# keyboard.net
KiCad netlist of a schematic drawn in Altium Designer
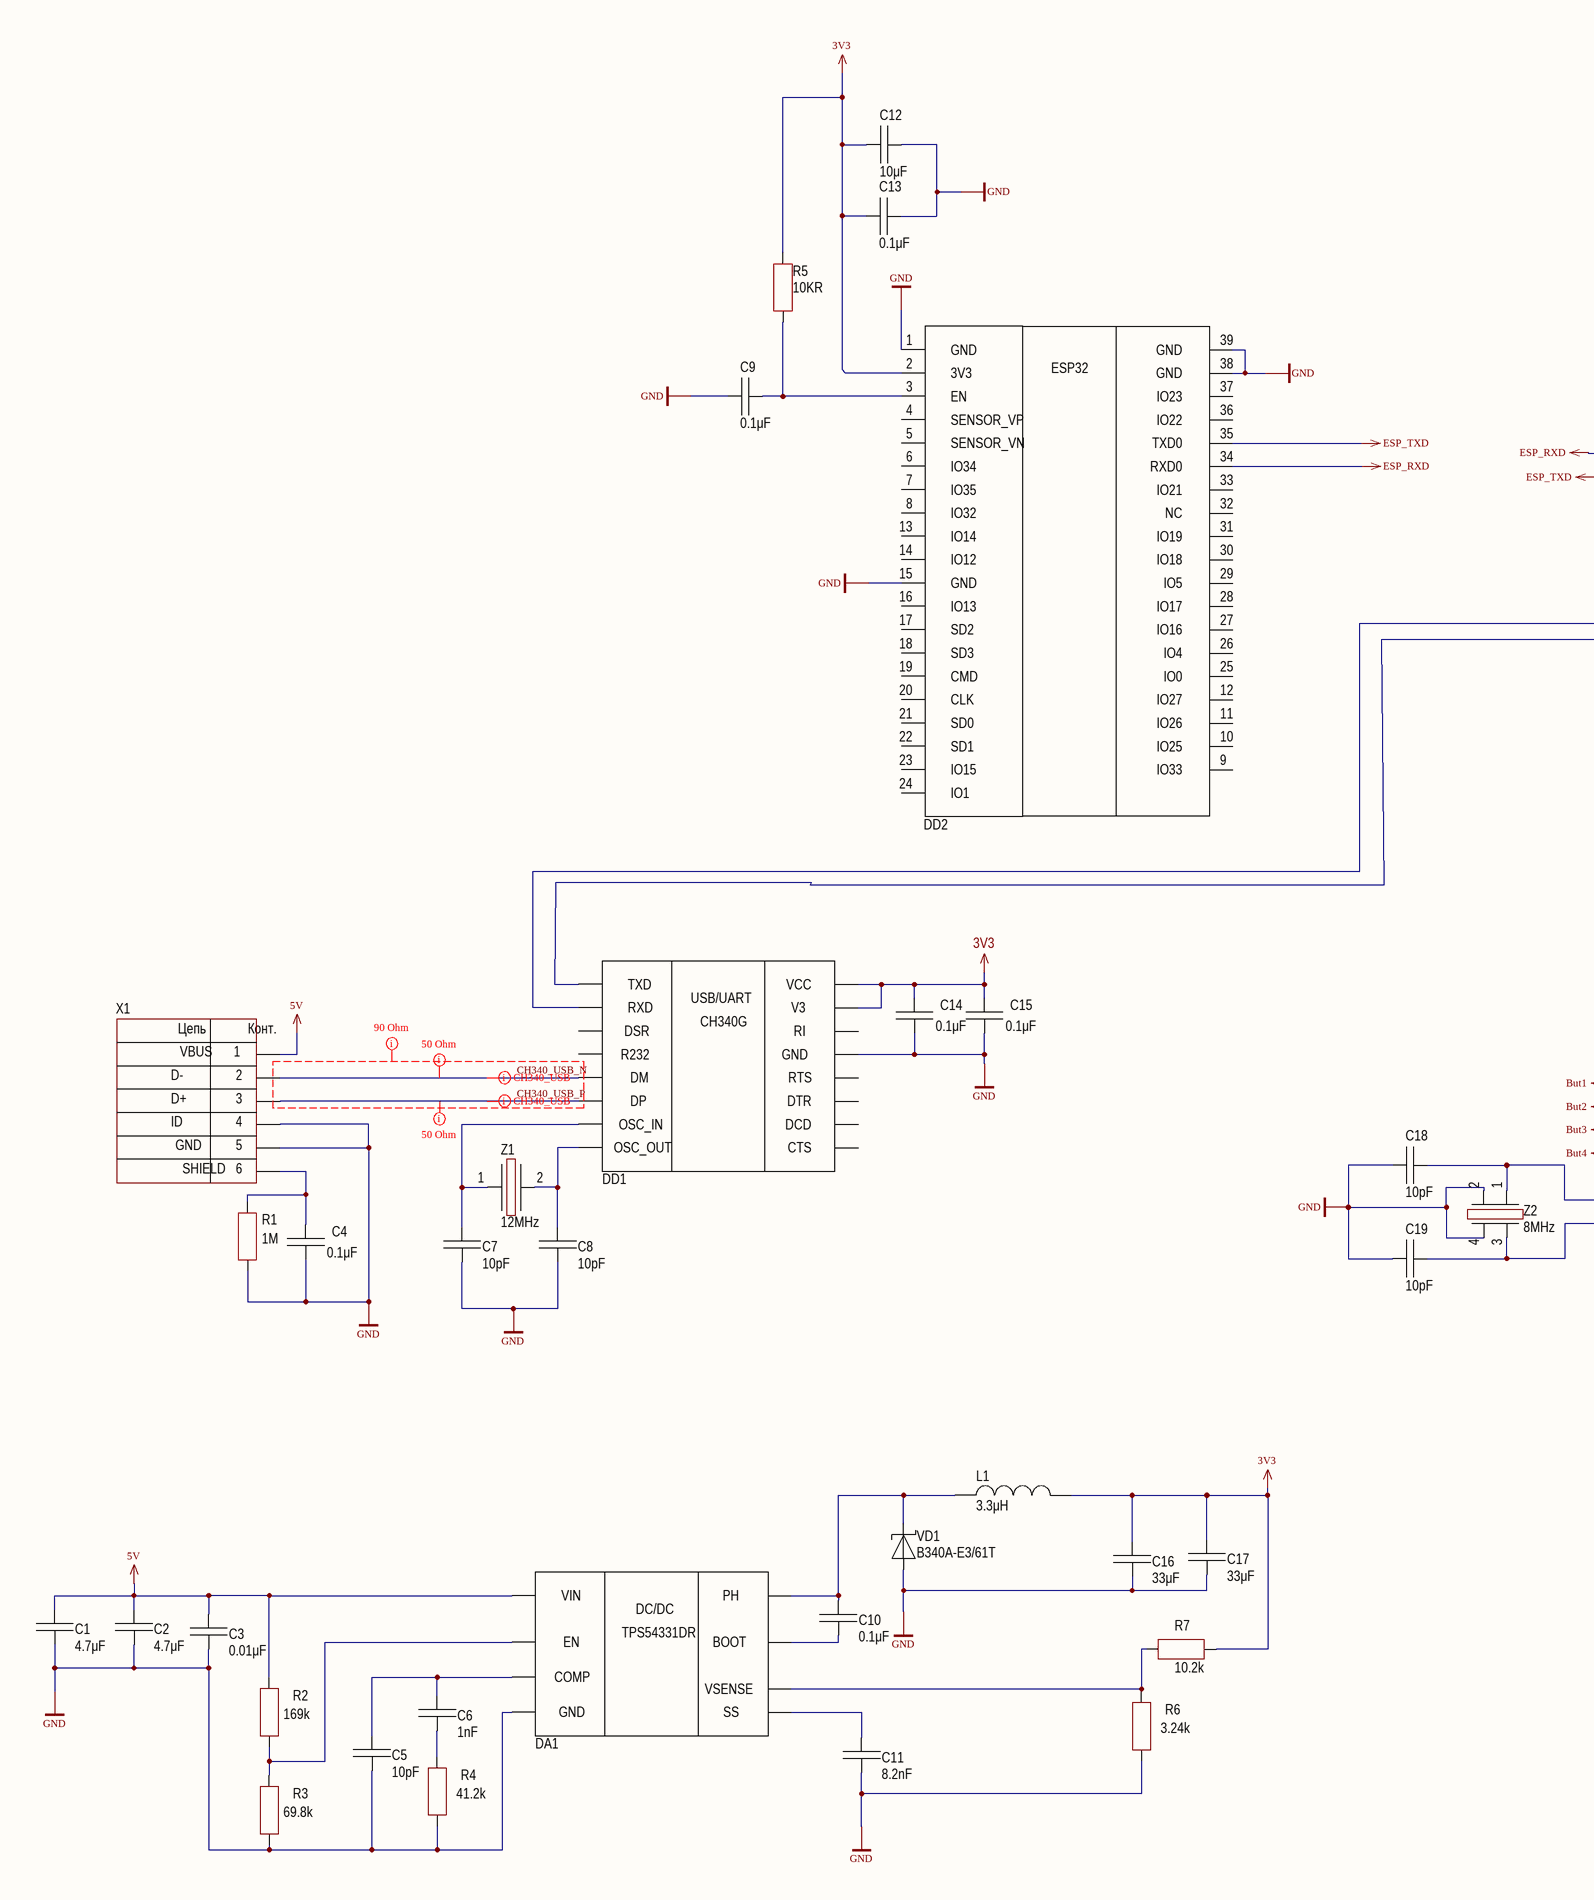
[diagram p0: keyboard.SchDoc, left]
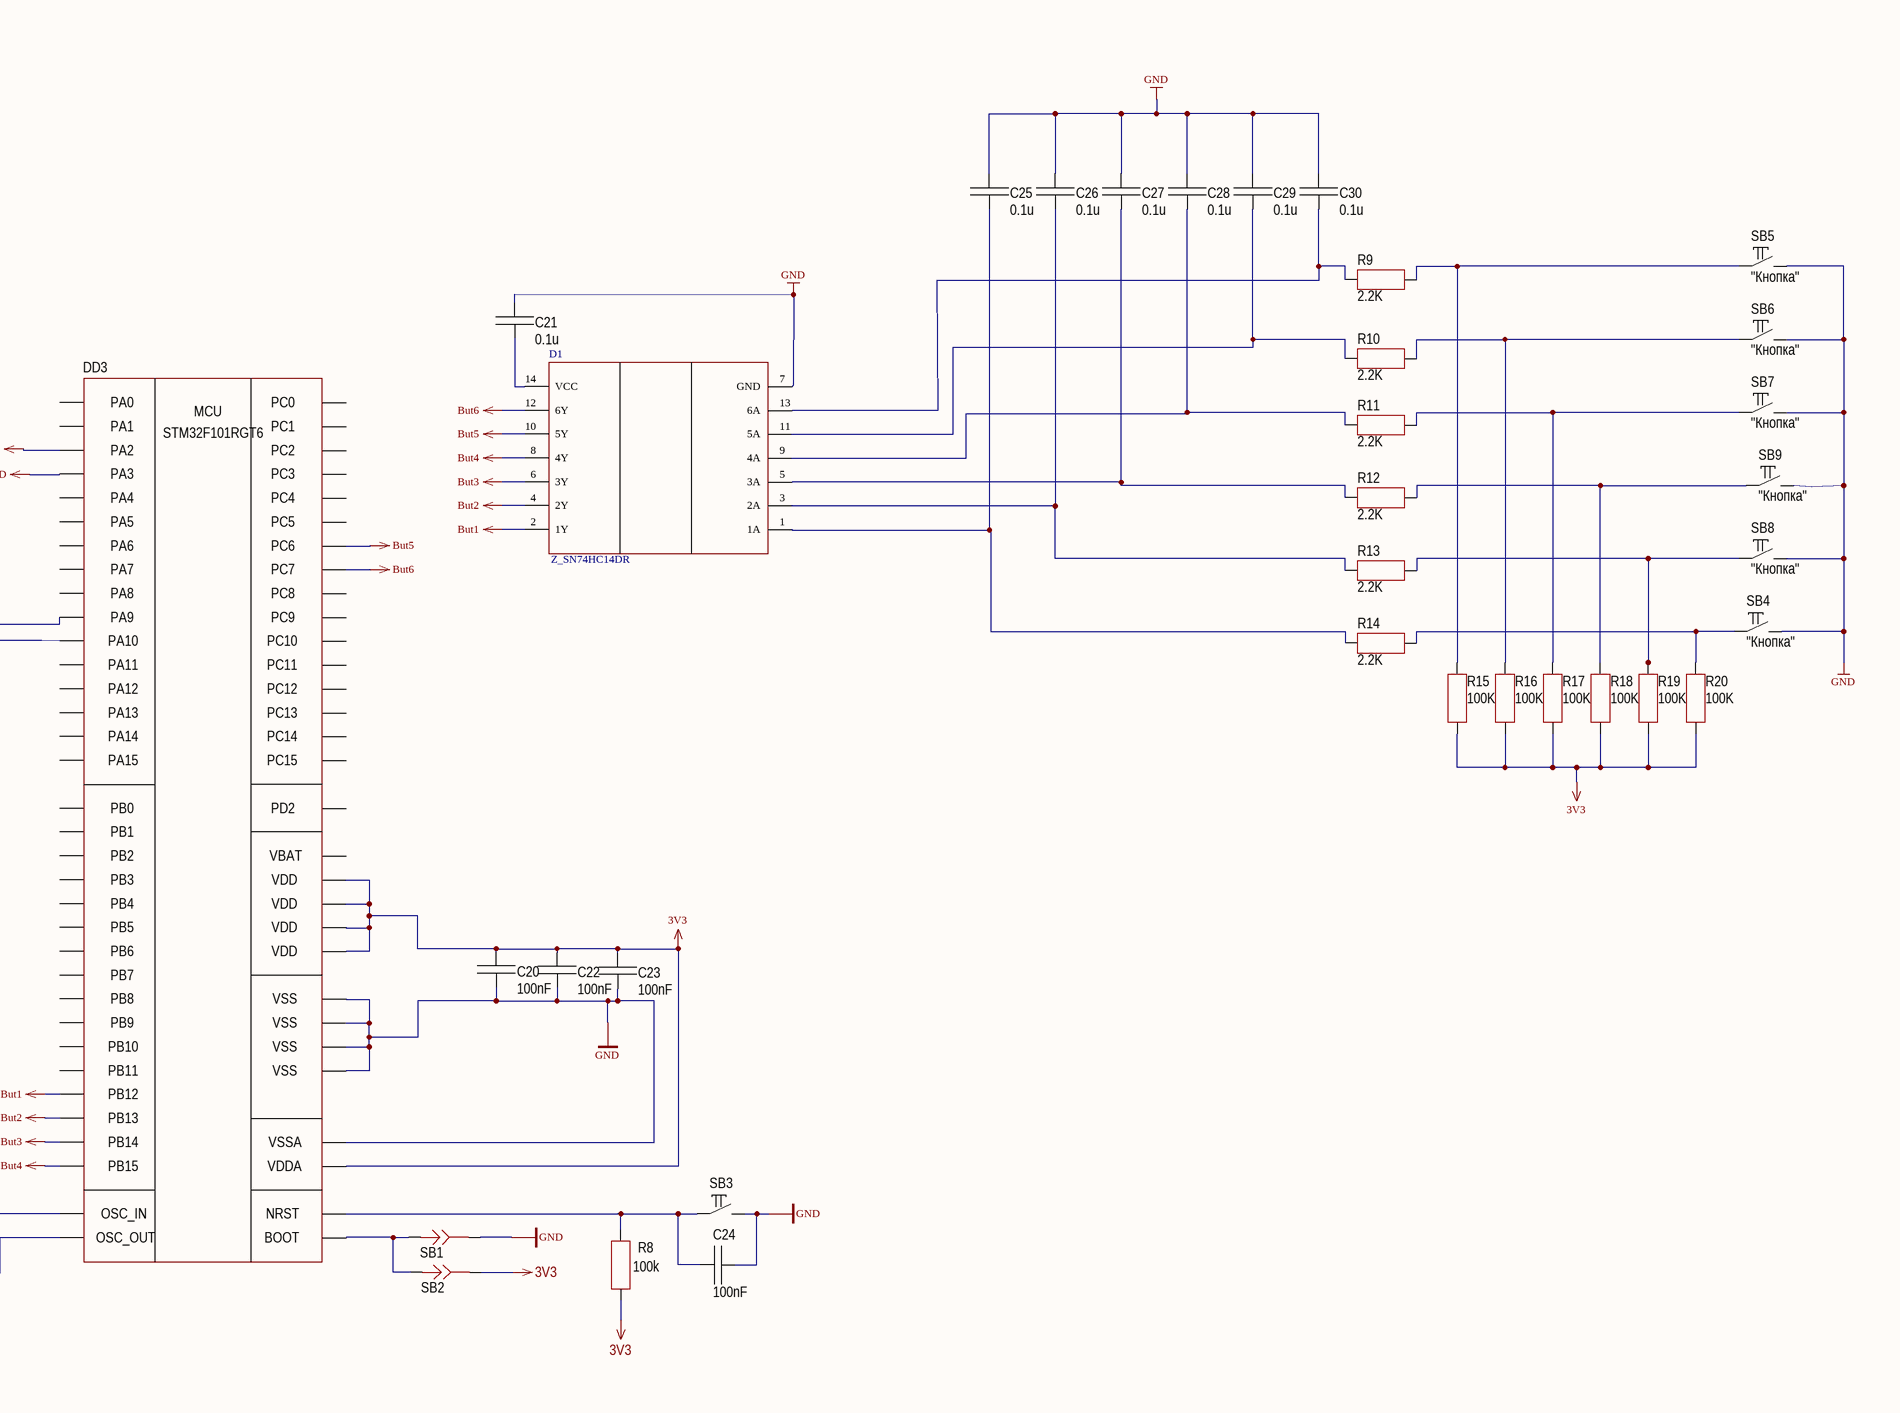
[diagram p1: keyboard.SchDoc, right]

(export (version "E")
  (design (tool "Eeschema 10.0.6"))
  (components
    (comp (ref "C1")
      (value "4.7μF")
      (footprint "CAP: 0603")
      (fields
        (field (name "VALUEMANUFACTURERPARTNUMBER") "Ceramic capacitor, 4.7μF, X7R, ±10%, 16V, 0603, -55...+125°C")
        (field (name "TOLERANCE") "±10%")
        (field (name "VOLTAGE") "16V")
      )
      (libsource (lib "Sch_camr0d") (part "CAP_CERAMIC-SMD"))
    )
    (comp (ref "C2")
      (value "4.7μF")
      (footprint "CAP: 0603")
      (fields
        (field (name "VALUEMANUFACTURERPARTNUMBER") "Ceramic capacitor, 4.7μF, X7R, ±10%, 16V, 0603, -55...+125°C")
        (field (name "TOLERANCE") "±10%")
        (field (name "VOLTAGE") "16V")
      )
      (libsource (lib "Sch_camr0d") (part "CAP_CERAMIC-SMD"))
    )
    (comp (ref "C3")
      (value "0.01μF")
      (footprint "CAP: 0603")
      (fields
        (field (name "VALUEMANUFACTURERPARTNUMBER") "Ceramic capacitor, 0.01μF, X7R, ±10%, 16V, 0603, -55...+125°C")
        (field (name "TOLERANCE") "±10%")
        (field (name "VOLTAGE") "16V")
      )
      (libsource (lib "Sch_camr0d") (part "CAP_CERAMIC-SMD"))
    )
    (comp (ref "C4")
      (value "0.1μF")
      (footprint "CAP: 0603")
      (fields
        (field (name "VALUEMANUFACTURERPARTNUMBER") "Ceramic capacitor, 0.1μF, X7R, ±10%, 16V, 0603, -55...+125°C")
        (field (name "TOLERANCE") "±10%")
        (field (name "VOLTAGE") "16V")
      )
      (libsource (lib "Sch_camr0d") (part "CAP_CERAMIC-SMD"))
    )
    (comp (ref "C5")
      (value "10pF")
      (footprint "CAP: 0603")
      (fields
        (field (name "VALUEMANUFACTURERPARTNUMBER") "Ceramic capacitor, 10pF, X7R, ±10%, 16V, 0603, -55...+125°C")
        (field (name "TOLERANCE") "±10%")
        (field (name "VOLTAGE") "16V")
      )
      (libsource (lib "Sch_camr0d") (part "CAP_CERAMIC-SMD"))
    )
    (comp (ref "C6")
      (value "1nF")
      (footprint "CAP: 0603")
      (fields
        (field (name "VALUEMANUFACTURERPARTNUMBER") "Ceramic capacitor, 1nF, X7R, ±10%, 16V, 0603, -55...+125°C")
        (field (name "TOLERANCE") "±10%")
        (field (name "VOLTAGE") "16V")
      )
      (libsource (lib "Sch_camr0d") (part "CAP_CERAMIC-SMD"))
    )
    (comp (ref "C7")
      (value "10pF")
      (footprint "CAP: 0603")
      (fields
        (field (name "VALUEMANUFACTURERPARTNUMBER") "Ceramic capacitor, 10pF, X7R, ±10%, 16V, 0603, -55...+125°C")
        (field (name "TOLERANCE") "±10%")
        (field (name "VOLTAGE") "16V")
      )
      (libsource (lib "Sch_camr0d") (part "CAP_CERAMIC-SMD"))
    )
    (comp (ref "C8")
      (value "10pF")
      (footprint "CAP: 0603")
      (fields
        (field (name "VALUEMANUFACTURERPARTNUMBER") "Ceramic capacitor, 10pF, X7R, ±10%, 16V, 0603, -55...+125°C")
        (field (name "TOLERANCE") "±10%")
        (field (name "VOLTAGE") "16V")
      )
      (libsource (lib "Sch_camr0d") (part "CAP_CERAMIC-SMD"))
    )
    (comp (ref "C9")
      (value "0.1μF")
      (footprint "CAP: 0603")
      (fields
        (field (name "VALUEMANUFACTURERPARTNUMBER") "Ceramic capacitor, 0.1μF, X7R, ±10%, 16V, 0603, -55...+125°C")
        (field (name "TOLERANCE") "±10%")
        (field (name "VOLTAGE") "16V")
      )
      (libsource (lib "Sch_camr0d") (part "CAP_CERAMIC-SMD"))
    )
    (comp (ref "C10")
      (value "0.1μF")
      (footprint "CAP: 0603")
      (fields
        (field (name "VALUEMANUFACTURERPARTNUMBER") "Ceramic capacitor, 0.1μF, X7R, ±10%, 16V, 0603, -55...+125°C")
        (field (name "TOLERANCE") "±10%")
        (field (name "VOLTAGE") "16V")
      )
      (libsource (lib "Sch_camr0d") (part "CAP_CERAMIC-SMD"))
    )
    (comp (ref "C11")
      (value "8.2nF")
      (footprint "CAP: 0603")
      (fields
        (field (name "VALUEMANUFACTURERPARTNUMBER") "Ceramic capacitor, 8.2nF, X7R, ±10%, 16V, 0603, -55...+125°C")
        (field (name "TOLERANCE") "±10%")
        (field (name "VOLTAGE") "16V")
      )
      (libsource (lib "Sch_camr0d") (part "CAP_CERAMIC-SMD"))
    )
    (comp (ref "C12")
      (value "10μF")
      (footprint "CAP: 0603")
      (fields
        (field (name "VALUEMANUFACTURERPARTNUMBER") "Ceramic capacitor, 10μF, X7R, ±10%, 16V, 0603, -55...+125°C")
        (field (name "TOLERANCE") "±10%")
        (field (name "VOLTAGE") "16V")
      )
      (libsource (lib "Sch_camr0d") (part "CAP_CERAMIC-SMD"))
    )
    (comp (ref "C13")
      (value "0.1μF")
      (footprint "CAP: 0603")
      (fields
        (field (name "VALUEMANUFACTURERPARTNUMBER") "Ceramic capacitor, 0.1μF, X7R, ±10%, 16V, 0603, -55...+125°C")
        (field (name "TOLERANCE") "±10%")
        (field (name "VOLTAGE") "16V")
      )
      (libsource (lib "Sch_camr0d") (part "CAP_CERAMIC-SMD"))
    )
    (comp (ref "C14")
      (value "0.1μF")
      (footprint "CAP: 0603")
      (fields
        (field (name "VALUEMANUFACTURERPARTNUMBER") "Ceramic capacitor, 0.1μF, X7R, ±10%, 16V, 0603, -55...+125°C")
        (field (name "TOLERANCE") "±10%")
        (field (name "VOLTAGE") "16V")
      )
      (libsource (lib "Sch_camr0d") (part "CAP_CERAMIC-SMD"))
    )
    (comp (ref "C15")
      (value "0.1μF")
      (footprint "CAP: 0603")
      (fields
        (field (name "VALUEMANUFACTURERPARTNUMBER") "Ceramic capacitor, 0.1μF, X7R, ±10%, 16V, 0603, -55...+125°C")
        (field (name "TOLERANCE") "±10%")
        (field (name "VOLTAGE") "16V")
      )
      (libsource (lib "Sch_camr0d") (part "CAP_CERAMIC-SMD"))
    )
    (comp (ref "C16")
      (value "33μF")
      (footprint "CAP: 0805")
      (fields
        (field (name "VALUEMANUFACTURERPARTNUMBER") "Ceramic capacitor, 33μF, X7R, ±10%, 16V, 0805, -55...+125°C")
        (field (name "TOLERANCE") "±10%")
        (field (name "VOLTAGE") "16V")
      )
      (libsource (lib "") (part "CAP_CERAMIC-SMD_1"))
    )
    (comp (ref "C17")
      (value "33μF")
      (footprint "CAP: 0805")
      (fields
        (field (name "VALUEMANUFACTURERPARTNUMBER") "Ceramic capacitor, 33μF, X7R, ±10%, 16V, 0805, -55...+125°C")
        (field (name "TOLERANCE") "±10%")
        (field (name "VOLTAGE") "16V")
      )
      (libsource (lib "Sch_camr0d") (part "CAP_CERAMIC-SMD"))
    )
    (comp (ref "C18")
      (value "10pF")
      (footprint "CAP: 0603")
      (fields
        (field (name "VALUEMANUFACTURERPARTNUMBER") "Ceramic capacitor, 10pF, X7R, ±10%, 16V, 0603, -55...+125°C")
        (field (name "TOLERANCE") "±10%")
        (field (name "VOLTAGE") "16V")
      )
      (libsource (lib "Sch_camr0d") (part "CAP_CERAMIC-SMD"))
    )
    (comp (ref "C19")
      (value "10pF")
      (footprint "CAP: 0603")
      (fields
        (field (name "VALUEMANUFACTURERPARTNUMBER") "Ceramic capacitor, 10pF, X7R, ±10%, 16V, 0603, -55...+125°C")
        (field (name "TOLERANCE") "±10%")
        (field (name "VOLTAGE") "16V")
      )
      (libsource (lib "Sch_camr0d") (part "CAP_CERAMIC-SMD"))
    )
    (comp (ref "C20")
      (value "100nF")
      (footprint "CAP: 0603")
      (fields
        (field (name "VALUEMANUFACTURERPARTNUMBER") "Ceramic capacitor, 100nF, X7R, ±10%, 16V, 0603, -55...+125°C")
        (field (name "TOLERANCE") "±10%")
        (field (name "VOLTAGE") "16V")
      )
      (libsource (lib "Sch_camr0d") (part "CAP_CERAMIC-SMD"))
    )
    (comp (ref "C21")
      (value "0.1u")
      (footprint "CAP: 0805")
      (fields
        (field (name "VALUEMANUFACTURERPARTNUMBER") "Ceramic capacitor, 0.1u, X7R, ±10%, 16V, 0805, -55...+125°C")
        (field (name "TOLERANCE") "±10%")
        (field (name "VOLTAGE") "16V")
      )
      (libsource (lib "Schlib1") (part "Ceramic_0805"))
    )
    (comp (ref "C22")
      (value "100nF")
      (footprint "CAP: 0603")
      (fields
        (field (name "VALUEMANUFACTURERPARTNUMBER") "Ceramic capacitor, 100nF, X7R, ±10%, 16V, 0603, -55...+125°C")
        (field (name "TOLERANCE") "±10%")
        (field (name "VOLTAGE") "16V")
      )
      (libsource (lib "Sch_camr0d") (part "CAP_CERAMIC-SMD"))
    )
    (comp (ref "C23")
      (value "100nF")
      (footprint "CAP: 0603")
      (fields
        (field (name "VALUEMANUFACTURERPARTNUMBER") "Ceramic capacitor, 100nF, X7R, ±10%, 16V, 0603, -55...+125°C")
        (field (name "TOLERANCE") "±10%")
        (field (name "VOLTAGE") "16V")
      )
      (libsource (lib "Sch_camr0d") (part "CAP_CERAMIC-SMD"))
    )
    (comp (ref "C24")
      (value "100nF")
      (footprint "CAP: 0603")
      (fields
        (field (name "VALUEMANUFACTURERPARTNUMBER") "Ceramic capacitor, 100nF, X7R, ±10%, 16V, 0603, -55...+125°C")
        (field (name "TOLERANCE") "±10%")
        (field (name "VOLTAGE") "16V")
      )
      (libsource (lib "Sch_camr0d") (part "CAP_CERAMIC-SMD"))
    )
    (comp (ref "C25")
      (value "0.1u")
      (footprint "CAP: 0805")
      (fields
        (field (name "VALUEMANUFACTURERPARTNUMBER") "Ceramic capacitor, 0.1u, X7R, ±10%, 16V, 0805, -55...+125°C")
        (field (name "TOLERANCE") "±10%")
        (field (name "VOLTAGE") "16V")
      )
      (libsource (lib "Schlib1") (part "Ceramic_0805"))
    )
    (comp (ref "C26")
      (value "0.1u")
      (footprint "CAP: 0805")
      (fields
        (field (name "VALUEMANUFACTURERPARTNUMBER") "Ceramic capacitor, 0.1u, X7R, ±10%, 16V, 0805, -55...+125°C")
        (field (name "TOLERANCE") "±10%")
        (field (name "VOLTAGE") "16V")
      )
      (libsource (lib "Schlib1") (part "Ceramic_0805"))
    )
    (comp (ref "C27")
      (value "0.1u")
      (footprint "CAP: 0805")
      (fields
        (field (name "VALUEMANUFACTURERPARTNUMBER") "Ceramic capacitor, 0.1u, X7R, ±10%, 16V, 0805, -55...+125°C")
        (field (name "TOLERANCE") "±10%")
        (field (name "VOLTAGE") "16V")
      )
      (libsource (lib "Schlib1") (part "Ceramic_0805"))
    )
    (comp (ref "C28")
      (value "0.1u")
      (footprint "CAP: 0805")
      (fields
        (field (name "VALUEMANUFACTURERPARTNUMBER") "Ceramic capacitor, 0.1u, X7R, ±10%, 16V, 0805, -55...+125°C")
        (field (name "TOLERANCE") "±10%")
        (field (name "VOLTAGE") "16V")
      )
      (libsource (lib "Schlib1") (part "Ceramic_0805"))
    )
    (comp (ref "C29")
      (value "0.1u")
      (footprint "CAP: 0805")
      (fields
        (field (name "VALUEMANUFACTURERPARTNUMBER") "Ceramic capacitor, 0.1u, X7R, ±10%, 16V, 0805, -55...+125°C")
        (field (name "TOLERANCE") "±10%")
        (field (name "VOLTAGE") "16V")
      )
      (libsource (lib "Schlib1") (part "Ceramic_0805"))
    )
    (comp (ref "C30")
      (value "0.1u")
      (footprint "CAP: 0805")
      (fields
        (field (name "VALUEMANUFACTURERPARTNUMBER") "Ceramic capacitor, 0.1u, X7R, ±10%, 16V, 0805, -55...+125°C")
        (field (name "TOLERANCE") "±10%")
        (field (name "VOLTAGE") "16V")
      )
      (libsource (lib "Schlib1") (part "Ceramic_0805"))
    )
    (comp (ref "D1")
      (value "Z_SN74HC14DR")
      (footprint "14-SOIC")
      (description "Schmitt trigger")
      (libsource (lib "Sch_camr0d") (part "Z_SN74HC14DR"))
    )
    (comp (ref "DA1")
      (value "~")
      (footprint "8-SOIC")
      (description "Step Down DC/DC")
      (fields
        (field (name "MANUFACTURER") "TexasInstruments")
        (field (name "VALUEMANUFACTURERPARTNUMBER") "DC/DC, , , , , , , -40...+150°C, SOIC-8")
      )
      (libsource (lib "Sch_camr0d") (part "DC/DC_TPS54331DR"))
    )
    (comp (ref "DD1")
      (value "~")
      (footprint "16-SO")
      (description "USB-to-UART")
      (fields
        (field (name "MANUFACTURER") "DreamCity Innovations")
        (field (name "VALUEMANUFACTURERPARTNUMBER") "IC usb-to-uart bridge, USB2.0, 3...3.6V, -40...+85°C, SOIC-16")
      )
      (libsource (lib "Sch_camr0d") (part "USB/UART_CH340G"))
    )
    (comp (ref "DD2")
      (value "Z_ESP32-WROOM-32")
      (footprint "ESP32-WROOM-32")
      (libsource (lib "Sch_camr0d") (part "Z_ESP32-WROOM-32"))
    )
    (comp (ref "DD3")
      (value "~")
      (footprint "64-LQFP")
      (description "Cortex-M3")
      (fields
        (field (name "MANUFACTURER") "STMicroelectronics")
        (field (name "VALUEMANUFACTURERPARTNUMBER") "IC microcontroller, 32-Bit, Cortex-M3, 72MHz, 128KB, 20KB, 2...3.6V, -40...+85°C, 64-LQFP")
        (field (name "PARTNUMBER") "STM32F101RGT6")
      )
      (libsource (lib "Sch_camr0d") (part "MCU_STM32F101RGT6"))
    )
    (comp (ref "L1")
      (value "3.3μH")
      (footprint "IND: ETQP3MXXXKVN")
      (fields
        (field (name "MANUFACTURER") "Murata Electronics")
        (field (name "PARTNUMBER") "ETQP3M3R3KVN")
        (field (name "VALUEMANUFACTURERPARTNUMBER") "Fixed inductor, 3.3μH, ±5%, SMD, 5A, -55...+155°C")
      )
      (libsource (lib "Sch_camr0d") (part "IND_ETQP3M6R8KVN"))
    )
    (comp (ref "R1")
      (value "1M")
      (footprint "RES: 0603")
      (fields
        (field (name "MANUFACTURER") "Yageo")
        (field (name "PARTNUMBER") "RC0603JR-07100RL")
        (field (name "VALUEMANUFACTURERPARTNUMBER") "Resistor film, 1M, ±5%, 0603, 0.1W, -55...+125°C")
      )
      (libsource (lib "Sch_camr0d") (part "RES_SMD"))
    )
    (comp (ref "R2")
      (value "169k")
      (footprint "RES: 0603")
      (fields
        (field (name "MANUFACTURER") "Yageo")
        (field (name "PARTNUMBER") "RC0603JR-07100RL")
        (field (name "VALUEMANUFACTURERPARTNUMBER") "Resistor film, 169k, ±5%, 0603, 0.1W, -55...+125°C")
      )
      (libsource (lib "Sch_camr0d") (part "RES-SMD"))
    )
    (comp (ref "R3")
      (value "69.8k")
      (footprint "RES: 0603")
      (fields
        (field (name "MANUFACTURER") "Yageo")
        (field (name "PARTNUMBER") "RC0603JR-07100RL")
        (field (name "VALUEMANUFACTURERPARTNUMBER") "Resistor film, 69.8k, ±5%, 0603, 0.1W, -55...+125°C")
      )
      (libsource (lib "Sch_camr0d") (part "RES-SMD"))
    )
    (comp (ref "R4")
      (value "41.2k")
      (footprint "RES: 0603")
      (fields
        (field (name "MANUFACTURER") "Yageo")
        (field (name "PARTNUMBER") "RC0603JR-07100RL")
        (field (name "VALUEMANUFACTURERPARTNUMBER") "Resistor film, 41.2k, ±5%, 0603, 0.1W, -55...+125°C")
      )
      (libsource (lib "Sch_camr0d") (part "RES-SMD"))
    )
    (comp (ref "R5")
      (value "10KR")
      (footprint "RES: 0603")
      (fields
        (field (name "MANUFACTURER") "Yageo")
        (field (name "PARTNUMBER") "RC0603JR-07100RL")
        (field (name "VALUEMANUFACTURERPARTNUMBER") "Resistor film, 10KR, ±5%, 0603, 0.1W, -55...+125°C")
      )
      (libsource (lib "Sch_camr0d") (part "RES_SMD"))
    )
    (comp (ref "R6")
      (value "3.24k")
      (footprint "RES: 0603")
      (fields
        (field (name "MANUFACTURER") "Yageo")
        (field (name "PARTNUMBER") "RC0603JR-07100RL")
        (field (name "VALUEMANUFACTURERPARTNUMBER") "Resistor film, 3.24k, ±5%, 0603, 0.1W, -55...+125°C")
      )
      (libsource (lib "") (part "RES-SMD_1"))
    )
    (comp (ref "R7")
      (value "10.2k")
      (footprint "RES: 0603")
      (fields
        (field (name "MANUFACTURER") "Yageo")
        (field (name "PARTNUMBER") "RC0603JR-07100RL")
        (field (name "VALUEMANUFACTURERPARTNUMBER") "Resistor film, 10.2k, ±5%, 0603, 0.1W, -55...+125°C")
      )
      (libsource (lib "") (part "RES-SMD_2"))
    )
    (comp (ref "R8")
      (value "100k")
      (footprint "RES: 0603")
      (fields
        (field (name "MANUFACTURER") "Yageo")
        (field (name "PARTNUMBER") "RC0603JR-07100RL")
        (field (name "VALUEMANUFACTURERPARTNUMBER") "Resistor film, 100k, ±5%, 0603, 0.1W, -55...+125°C")
      )
      (libsource (lib "Sch_camr0d") (part "RES_SMD"))
    )
    (comp (ref "R9")
      (value "2.2K")
      (footprint "RES: 0603")
      (fields
        (field (name "MANUFACTURER") "Yageo")
        (field (name "PARTNUMBER") "RC0603JR-07100RL")
        (field (name "VALUEMANUFACTURERPARTNUMBER") "Resistor film, 2.2K, ±5%, 0603, 0.1W, -55...+125°C")
      )
      (libsource (lib "") (part "RES_SMD_1"))
    )
    (comp (ref "R10")
      (value "2.2K")
      (footprint "RES: 0603")
      (fields
        (field (name "MANUFACTURER") "Yageo")
        (field (name "PARTNUMBER") "RC0603JR-07100RL")
        (field (name "VALUEMANUFACTURERPARTNUMBER") "Resistor film, 2.2K, ±5%, 0603, 0.1W, -55...+125°C")
      )
      (libsource (lib "") (part "RES_SMD_1"))
    )
    (comp (ref "R11")
      (value "2.2K")
      (footprint "RES: 0603")
      (fields
        (field (name "MANUFACTURER") "Yageo")
        (field (name "PARTNUMBER") "RC0603JR-07100RL")
        (field (name "VALUEMANUFACTURERPARTNUMBER") "Resistor film, 2.2K, ±5%, 0603, 0.1W, -55...+125°C")
      )
      (libsource (lib "") (part "RES_SMD_1"))
    )
    (comp (ref "R12")
      (value "2.2K")
      (footprint "RES: 0603")
      (fields
        (field (name "MANUFACTURER") "Yageo")
        (field (name "PARTNUMBER") "RC0603JR-07100RL")
        (field (name "VALUEMANUFACTURERPARTNUMBER") "Resistor film, 2.2K, ±5%, 0603, 0.1W, -55...+125°C")
      )
      (libsource (lib "") (part "RES_SMD_1"))
    )
    (comp (ref "R13")
      (value "2.2K")
      (footprint "RES: 0603")
      (fields
        (field (name "MANUFACTURER") "Yageo")
        (field (name "PARTNUMBER") "RC0603JR-07100RL")
        (field (name "VALUEMANUFACTURERPARTNUMBER") "Resistor film, 2.2K, ±5%, 0603, 0.1W, -55...+125°C")
      )
      (libsource (lib "") (part "RES_SMD_1"))
    )
    (comp (ref "R14")
      (value "2.2K")
      (footprint "RES: 0603")
      (fields
        (field (name "MANUFACTURER") "Yageo")
        (field (name "PARTNUMBER") "RC0603JR-07100RL")
        (field (name "VALUEMANUFACTURERPARTNUMBER") "Resistor film, 2.2K, ±5%, 0603, 0.1W, -55...+125°C")
      )
      (libsource (lib "") (part "RES_SMD_1"))
    )
    (comp (ref "R15")
      (value "100K")
      (footprint "RES: 0603")
      (fields
        (field (name "MANUFACTURER") "Yageo")
        (field (name "PARTNUMBER") "RC0603JR-07100RL")
        (field (name "VALUEMANUFACTURERPARTNUMBER") "Resistor film, 100K, ±5%, 0603, 0.1W, -55...+125°C")
      )
      (libsource (lib "Sch_camr0d") (part "RES_SMD"))
    )
    (comp (ref "R16")
      (value "100K")
      (footprint "RES: 0603")
      (fields
        (field (name "MANUFACTURER") "Yageo")
        (field (name "PARTNUMBER") "RC0603JR-07100RL")
        (field (name "VALUEMANUFACTURERPARTNUMBER") "Resistor film, 100K, ±5%, 0603, 0.1W, -55...+125°C")
      )
      (libsource (lib "Sch_camr0d") (part "RES_SMD"))
    )
    (comp (ref "R17")
      (value "100K")
      (footprint "RES: 0603")
      (fields
        (field (name "MANUFACTURER") "Yageo")
        (field (name "PARTNUMBER") "RC0603JR-07100RL")
        (field (name "VALUEMANUFACTURERPARTNUMBER") "Resistor film, 100K, ±5%, 0603, 0.1W, -55...+125°C")
      )
      (libsource (lib "Sch_camr0d") (part "RES_SMD"))
    )
    (comp (ref "R18")
      (value "100K")
      (footprint "RES: 0603")
      (fields
        (field (name "MANUFACTURER") "Yageo")
        (field (name "PARTNUMBER") "RC0603JR-07100RL")
        (field (name "VALUEMANUFACTURERPARTNUMBER") "Resistor film, 100K, ±5%, 0603, 0.1W, -55...+125°C")
      )
      (libsource (lib "Sch_camr0d") (part "RES_SMD"))
    )
    (comp (ref "R19")
      (value "100K")
      (footprint "RES: 0603")
      (fields
        (field (name "MANUFACTURER") "Yageo")
        (field (name "PARTNUMBER") "RC0603JR-07100RL")
        (field (name "VALUEMANUFACTURERPARTNUMBER") "Resistor film, 100K, ±5%, 0603, 0.1W, -55...+125°C")
      )
      (libsource (lib "Sch_camr0d") (part "RES_SMD"))
    )
    (comp (ref "R20")
      (value "100K")
      (footprint "RES: 0603")
      (fields
        (field (name "MANUFACTURER") "Yageo")
        (field (name "PARTNUMBER") "RC0603JR-07100RL")
        (field (name "VALUEMANUFACTURERPARTNUMBER") "Resistor film, 100K, ±5%, 0603, 0.1W, -55...+125°C")
      )
      (libsource (lib "Sch_camr0d") (part "RES_SMD"))
    )
    (comp (ref "SB1") (value "~") (footprint "RES: JMP") (libsource (lib "Sch_camr0d") (part "RES_JMP")))
    (comp (ref "SB2") (value "~") (footprint "RES: JMP") (libsource (lib "Sch_camr0d") (part "RES_JMP")))
    (comp (ref "SB3")
      (value "~")
      (footprint "BUT: 6x6 SMD")
      (description "Button")
      (fields (field (name "MANUFACTURER") "TE Connectivity") (field (name "PARTNUMBER") "190533"))
      (libsource (lib "Sch_camr0d") (part "BUT_Tactile"))
    )
    (comp (ref "SB4")
      (value "~")
      (footprint "BUT: 6x6 SMD")
      (description "Button")
      (fields
        (field (name "MANUFACTURER") "TE Connectivity")
        (field (name "PARTNUMBER") "190533")
        (field (name "COMMENTTEXT") "\"Кнопка\"")
      )
      (libsource (lib "Sch_camr0d") (part "BUT_Tactile"))
    )
    (comp (ref "SB5")
      (value "~")
      (footprint "BUT: 6x6 SMD")
      (description "Button")
      (fields
        (field (name "MANUFACTURER") "TE Connectivity")
        (field (name "PARTNUMBER") "190533")
        (field (name "COMMENTTEXT") "\"Кнопка\"")
      )
      (libsource (lib "Sch_camr0d") (part "BUT_Tactile"))
    )
    (comp (ref "SB6")
      (value "~")
      (footprint "BUT: 6x6 SMD")
      (description "Button")
      (fields
        (field (name "MANUFACTURER") "TE Connectivity")
        (field (name "PARTNUMBER") "190533")
        (field (name "COMMENTTEXT") "\"Кнопка\"")
      )
      (libsource (lib "Sch_camr0d") (part "BUT_Tactile"))
    )
    (comp (ref "SB7")
      (value "~")
      (footprint "BUT: 6x6 SMD")
      (description "Button")
      (fields
        (field (name "MANUFACTURER") "TE Connectivity")
        (field (name "PARTNUMBER") "190533")
        (field (name "COMMENTTEXT") "\"Кнопка\"")
      )
      (libsource (lib "Sch_camr0d") (part "BUT_Tactile"))
    )
    (comp (ref "SB8")
      (value "~")
      (footprint "BUT: 6x6 SMD")
      (description "Button")
      (fields
        (field (name "MANUFACTURER") "TE Connectivity")
        (field (name "PARTNUMBER") "190533")
        (field (name "COMMENTTEXT") "\"Кнопка\"")
      )
      (libsource (lib "Sch_camr0d") (part "BUT_Tactile"))
    )
    (comp (ref "SB9")
      (value "~")
      (footprint "BUT: 6x6 SMD")
      (description "Button")
      (fields
        (field (name "MANUFACTURER") "TE Connectivity")
        (field (name "PARTNUMBER") "190533")
        (field (name "COMMENTTEXT") "\"Кнопка\"")
      )
      (libsource (lib "Sch_camr0d") (part "BUT_Tactile"))
    )
    (comp (ref "VD1")
      (value "~")
      (footprint "DIODE: SMA")
      (fields
        (field (name "VALUEMANUFACTURERPARTNUMBER") "Schottky diode, 40V, 3A, 1V, 15pF, SOD-123, -65...+150°C")
        (field (name "VOLTAGE") "40V")
        (field (name "PARTNUMBER") "B340A-E3/61T")
      )
      (libsource (lib "Sch_camr0d") (part "DIODE_SCHOTTKY"))
    )
    (comp (ref "X1")
      (value "~")
      (footprint "CON: USB micro-A (ZX62-B-5PA)")
      (description "Micro USB type B")
      (fields (field (name "MANUFACTURER") "Hirose Electric") (field (name "PARTNUMBER") "544814"))
      (libsource (lib "Sch_camr0d") (part "CON_USB_micro_TypeB"))
    )
    (comp (ref "Z1")
      (value "~")
      (footprint "OSC: HC49/US")
      (fields
        (field (name "MANUFACTURER") "Abracon")
        (field (name "PARTNUMBER") "ABLS-12.000MHZ-B2-T")
        (field (name "VALUEMANUFACTURERPARTNUMBER") "Crystal, 12MHz, 18pF, ±20ppm, HC49/US, -40...+85°C")
        (field (name "FREQUENCY") "12MHz")
      )
      (libsource (lib "Sch_camr0d") (part "OSC_ABLS-12.000MHZ-B2-T"))
    )
    (comp (ref "Z2")
      (value "~")
      (footprint "OSC: 5032")
      (fields
        (field (name "MANUFACTURER") "Geyer")
        (field (name "PARTNUMBER") "12.89007")
        (field (name "VALUEMANUFACTURERPARTNUMBER") "Crystal, 8MHz, 16pF, ±30ppm, case 2016, -20...+70°C")
        (field (name "FREQUENCY") "8MHz")
      )
      (libsource (lib "Sch_camr0d") (part "OSC_12.89007"))
    )
  )
  (nets
    (net (code "1") (name "/CH340_USB_N") (class "Default")
      (node (ref "DD1") (pin "6") (pinfunction "DM_6") (pintype "passive"))
      (node (ref "X1") (pin "2") (pinfunction "2_2") (pintype "passive"))
    )
    (net (code "2") (name "/CH340_USB_P") (class "Default")
      (node (ref "DD1") (pin "5") (pinfunction "DP_5") (pintype "passive"))
      (node (ref "X1") (pin "3") (pinfunction "3_3") (pintype "passive"))
    )
    (net (code "3") (name "3V3") (class "Default")
      (node (ref "C12") (pin "2") (pinfunction "2_2") (pintype "power_in"))
      (node (ref "C13") (pin "2") (pinfunction "2_2") (pintype "power_in"))
      (node (ref "C14") (pin "2") (pinfunction "2_2") (pintype "power_in"))
      (node (ref "C15") (pin "2") (pinfunction "2_2") (pintype "power_in"))
      (node (ref "C16") (pin "2") (pinfunction "2_2") (pintype "power_in"))
      (node (ref "C17") (pin "2") (pinfunction "2_2") (pintype "power_in"))
      (node (ref "C20") (pin "2") (pinfunction "2_2") (pintype "power_in"))
      (node (ref "C22") (pin "2") (pinfunction "2_2") (pintype "power_in"))
      (node (ref "C23") (pin "2") (pinfunction "2_2") (pintype "power_in"))
      (node (ref "DD1") (pin "16") (pinfunction "VCC_16") (pintype "passive"))
      (node (ref "DD1") (pin "4") (pinfunction "V3_4") (pintype "passive"))
      (node (ref "DD2") (pin "2") (pinfunction "3V3_2") (pintype "passive"))
      (node (ref "DD3") (pin "13") (pinfunction "VDDA_13") (pintype "power_in"))
      (node (ref "DD3") (pin "19") (pinfunction "VDD_19") (pintype "power_in"))
      (node (ref "DD3") (pin "32") (pinfunction "VDD_32") (pintype "power_in"))
      (node (ref "DD3") (pin "48") (pinfunction "VDD_48") (pintype "power_in"))
      (node (ref "DD3") (pin "64") (pinfunction "VDD_64") (pintype "power_in"))
      (node (ref "L1") (pin "1") (pinfunction "1_1") (pintype "passive"))
      (node (ref "R15") (pin "1") (pinfunction "1_1") (pintype "passive"))
      (node (ref "R16") (pin "1") (pinfunction "1_1") (pintype "passive"))
      (node (ref "R17") (pin "1") (pinfunction "1_1") (pintype "passive"))
      (node (ref "R18") (pin "1") (pinfunction "1_1") (pintype "passive"))
      (node (ref "R19") (pin "1") (pinfunction "1_1") (pintype "passive"))
      (node (ref "R20") (pin "1") (pinfunction "1_1") (pintype "passive"))
      (node (ref "R5") (pin "2") (pinfunction "2_2") (pintype "passive"))
      (node (ref "R7") (pin "1") (pinfunction "1_1") (pintype "passive"))
      (node (ref "R8") (pin "1") (pinfunction "1_1") (pintype "passive"))
      (node (ref "SB2") (pin "2") (pinfunction "2_2") (pintype "passive"))
    )
    (net (code "4") (name "5V") (class "Default")
      (node (ref "C1") (pin "2") (pinfunction "2_2") (pintype "power_in"))
      (node (ref "C2") (pin "2") (pinfunction "2_2") (pintype "power_in"))
      (node (ref "C3") (pin "2") (pinfunction "2_2") (pintype "power_in"))
      (node (ref "DA1") (pin "2") (pinfunction "VIN_2") (pintype "passive"))
      (node (ref "R2") (pin "2") (pinfunction "2_2") (pintype "passive"))
      (node (ref "X1") (pin "1") (pintype "passive"))
    )
    (net (code "5") (name "But1") (class "Default")
      (node (ref "D1") (pin "2") (pinfunction "1Y_2") (pintype "passive"))
      (node (ref "DD3") (pin "33") (pinfunction "PB12_33") (pintype "passive"))
    )
    (net (code "6") (name "But2") (class "Default")
      (node (ref "D1") (pin "4") (pinfunction "2Y_4") (pintype "passive"))
      (node (ref "DD3") (pin "34") (pinfunction "PB13_34") (pintype "passive"))
    )
    (net (code "7") (name "But3") (class "Default")
      (node (ref "D1") (pin "6") (pinfunction "3Y_6") (pintype "passive"))
      (node (ref "DD3") (pin "35") (pinfunction "PB14_35") (pintype "passive"))
    )
    (net (code "8") (name "But4") (class "Default")
      (node (ref "D1") (pin "8") (pinfunction "4Y_8") (pintype "passive"))
      (node (ref "DD3") (pin "36") (pinfunction "PB15_36") (pintype "passive"))
    )
    (net (code "9") (name "But5") (class "Default")
      (node (ref "D1") (pin "10") (pinfunction "5Y_10") (pintype "passive"))
      (node (ref "DD3") (pin "37") (pinfunction "PC6_37") (pintype "passive"))
    )
    (net (code "10") (name "But6") (class "Default")
      (node (ref "D1") (pin "12") (pinfunction "6Y_12") (pintype "passive"))
      (node (ref "DD3") (pin "38") (pinfunction "PC7_38") (pintype "passive"))
    )
    (net (code "11") (name "ESP_RXD") (class "Default")
      (node (ref "DD2") (pin "34") (pinfunction "RXD0_34") (pintype "passive"))
      (node (ref "DD3") (pin "16") (pinfunction "PA2_16") (pintype "passive"))
    )
    (net (code "12") (name "ESP_TXD") (class "Default")
      (node (ref "DD2") (pin "35") (pinfunction "TXD0_35") (pintype "passive"))
      (node (ref "DD3") (pin "17") (pinfunction "PA3_17") (pintype "passive"))
    )
    (net (code "13") (name "GND") (class "Default")
      (node (ref "C1") (pin "1") (pinfunction "1_1") (pintype "power_in"))
      (node (ref "C11") (pin "1") (pinfunction "1_1") (pintype "power_in"))
      (node (ref "C12") (pin "1") (pinfunction "1_1") (pintype "power_in"))
      (node (ref "C13") (pin "1") (pinfunction "1_1") (pintype "power_in"))
      (node (ref "C14") (pin "1") (pinfunction "1_1") (pintype "power_in"))
      (node (ref "C15") (pin "1") (pinfunction "1_1") (pintype "power_in"))
      (node (ref "C16") (pin "1") (pinfunction "1_1") (pintype "power_in"))
      (node (ref "C17") (pin "1") (pinfunction "1_1") (pintype "power_in"))
      (node (ref "C18") (pin "1") (pinfunction "1_1") (pintype "power_in"))
      (node (ref "C19") (pin "1") (pinfunction "1_1") (pintype "power_in"))
      (node (ref "C2") (pin "1") (pinfunction "1_1") (pintype "power_in"))
      (node (ref "C20") (pin "1") (pinfunction "1_1") (pintype "power_in"))
      (node (ref "C21") (pin "1") (pinfunction "1_1") (pintype "power_in"))
      (node (ref "C22") (pin "1") (pinfunction "1_1") (pintype "power_in"))
      (node (ref "C23") (pin "1") (pinfunction "1_1") (pintype "power_in"))
      (node (ref "C24") (pin "1") (pinfunction "1_1") (pintype "power_in"))
      (node (ref "C25") (pin "1") (pinfunction "1_1") (pintype "power_in"))
      (node (ref "C26") (pin "1") (pinfunction "1_1") (pintype "power_in"))
      (node (ref "C27") (pin "1") (pinfunction "1_1") (pintype "power_in"))
      (node (ref "C28") (pin "1") (pinfunction "1_1") (pintype "power_in"))
      (node (ref "C29") (pin "1") (pinfunction "1_1") (pintype "power_in"))
      (node (ref "C3") (pin "1") (pinfunction "1_1") (pintype "power_in"))
      (node (ref "C30") (pin "1") (pinfunction "1_1") (pintype "power_in"))
      (node (ref "C4") (pin "1") (pinfunction "1_1") (pintype "power_in"))
      (node (ref "C5") (pin "1") (pinfunction "1_1") (pintype "power_in"))
      (node (ref "C7") (pin "1") (pinfunction "1_1") (pintype "power_in"))
      (node (ref "C8") (pin "1") (pinfunction "1_1") (pintype "power_in"))
      (node (ref "C9") (pin "2") (pinfunction "2_2") (pintype "power_in"))
      (node (ref "D1") (pin "7") (pinfunction "GND_7") (pintype "passive"))
      (node (ref "DA1") (pin "7") (pinfunction "GND_7") (pintype "passive"))
      (node (ref "DD1") (pin "1") (pinfunction "GND_1") (pintype "passive"))
      (node (ref "DD2") (pin "1") (pinfunction "GND_1") (pintype "passive"))
      (node (ref "DD2") (pin "15") (pinfunction "GND_15") (pintype "passive"))
      (node (ref "DD2") (pin "38") (pinfunction "GND_38") (pintype "passive"))
      (node (ref "DD2") (pin "39") (pinfunction "GND_39") (pintype "passive"))
      (node (ref "DD3") (pin "12") (pinfunction "VSSA_12") (pintype "power_in"))
      (node (ref "DD3") (pin "18") (pinfunction "VSS_18") (pintype "power_in"))
      (node (ref "DD3") (pin "31") (pinfunction "VSS_31") (pintype "power_in"))
      (node (ref "DD3") (pin "47") (pinfunction "VSS_47") (pintype "power_in"))
      (node (ref "DD3") (pin "63") (pinfunction "VSS_63") (pintype "power_in"))
      (node (ref "R1") (pin "1") (pinfunction "1_1") (pintype "passive"))
      (node (ref "R3") (pin "1") (pinfunction "1_1") (pintype "passive"))
      (node (ref "R4") (pin "1") (pinfunction "1_1") (pintype "passive"))
      (node (ref "R6") (pin "2") (pinfunction "2_2") (pintype "passive"))
      (node (ref "SB1") (pin "2") (pinfunction "2_2") (pintype "passive"))
      (node (ref "SB3") (pin "2") (pinfunction "2_2") (pintype "passive"))
      (node (ref "SB4") (pin "2") (pinfunction "2_2") (pintype "passive"))
      (node (ref "SB5") (pin "2") (pinfunction "2_2") (pintype "passive"))
      (node (ref "SB6") (pin "2") (pinfunction "2_2") (pintype "passive"))
      (node (ref "SB7") (pin "2") (pinfunction "2_2") (pintype "passive"))
      (node (ref "SB8") (pin "2") (pinfunction "2_2") (pintype "passive"))
      (node (ref "SB9") (pin "2") (pinfunction "2_2") (pintype "passive"))
      (node (ref "VD1") (pin "1") (pinfunction "1_1") (pintype "passive"))
      (node (ref "X1") (pin "4") (pinfunction "4_4") (pintype "passive"))
      (node (ref "X1") (pin "5") (pinfunction "5_5") (pintype "passive"))
      (node (ref "Z2") (pin "2") (pinfunction "2_2") (pintype "passive"))
      (node (ref "Z2") (pin "4") (pinfunction "4_4") (pintype "passive"))
    )
    (net (code "14") (name "Net-(C4-Pad2)") (class "Default")
      (node (ref "C4") (pin "2") (pinfunction "2_2") (pintype "power_in"))
      (node (ref "R1") (pin "2") (pinfunction "2_2") (pintype "passive"))
      (node (ref "X1") (pin "0") (pinfunction "0_0") (pintype "passive"))
    )
    (net (code "15") (name "Net-(C6-Pad1)") (class "Default")
      (node (ref "C6") (pin "1") (pinfunction "1_1") (pintype "power_in"))
      (node (ref "R4") (pin "2") (pinfunction "2_2") (pintype "passive"))
    )
    (net (code "16") (name "Net-(D1-1A)") (class "Default")
      (node (ref "C25") (pin "2") (pinfunction "2_2") (pintype "power_in"))
      (node (ref "D1") (pin "1") (pinfunction "1A_1") (pintype "passive"))
      (node (ref "R14") (pin "1") (pinfunction "1_1") (pintype "passive"))
    )
    (net (code "17") (name "Net-(D1-2A)") (class "Default")
      (node (ref "C26") (pin "2") (pinfunction "2_2") (pintype "power_in"))
      (node (ref "D1") (pin "3") (pinfunction "2A_3") (pintype "passive"))
      (node (ref "R13") (pin "1") (pinfunction "1_1") (pintype "passive"))
    )
    (net (code "18") (name "Net-(D1-3A)") (class "Default")
      (node (ref "C27") (pin "2") (pinfunction "2_2") (pintype "power_in"))
      (node (ref "D1") (pin "5") (pinfunction "3A_5") (pintype "passive"))
      (node (ref "R12") (pin "1") (pinfunction "1_1") (pintype "passive"))
    )
    (net (code "19") (name "Net-(D1-4A)") (class "Default")
      (node (ref "C28") (pin "2") (pinfunction "2_2") (pintype "power_in"))
      (node (ref "D1") (pin "9") (pinfunction "4A_9") (pintype "passive"))
      (node (ref "R11") (pin "1") (pinfunction "1_1") (pintype "passive"))
    )
    (net (code "20") (name "Net-(D1-5A)") (class "Default")
      (node (ref "C29") (pin "2") (pinfunction "2_2") (pintype "power_in"))
      (node (ref "D1") (pin "11") (pinfunction "5A_11") (pintype "passive"))
      (node (ref "R10") (pin "1") (pinfunction "1_1") (pintype "passive"))
    )
    (net (code "21") (name "Net-(D1-6A)") (class "Default")
      (node (ref "C30") (pin "2") (pinfunction "2_2") (pintype "power_in"))
      (node (ref "D1") (pin "13") (pinfunction "6A_13") (pintype "passive"))
      (node (ref "R9") (pin "1") (pinfunction "1_1") (pintype "passive"))
    )
    (net (code "22") (name "Net-(D1-VCC)") (class "Default")
      (node (ref "C21") (pin "2") (pinfunction "2_2") (pintype "power_in"))
      (node (ref "D1") (pin "14") (pinfunction "VCC_14") (pintype "passive"))
    )
    (net (code "23") (name "Net-(DA1-BOOT)") (class "Default")
      (node (ref "C10") (pin "2") (pinfunction "2_2") (pintype "power_in"))
      (node (ref "DA1") (pin "1") (pinfunction "BOOT_1") (pintype "passive"))
    )
    (net (code "24") (name "Net-(DA1-COMP)") (class "Default")
      (node (ref "C5") (pin "2") (pinfunction "2_2") (pintype "power_in"))
      (node (ref "C6") (pin "2") (pinfunction "2_2") (pintype "power_in"))
      (node (ref "DA1") (pin "6") (pinfunction "COMP_6") (pintype "passive"))
    )
    (net (code "25") (name "Net-(DA1-EN)") (class "Default")
      (node (ref "DA1") (pin "3") (pinfunction "EN_3") (pintype "passive"))
      (node (ref "R2") (pin "1") (pinfunction "1_1") (pintype "passive"))
      (node (ref "R3") (pin "2") (pinfunction "2_2") (pintype "passive"))
    )
    (net (code "26") (name "Net-(DA1-PH)") (class "Default")
      (node (ref "C10") (pin "1") (pinfunction "1_1") (pintype "power_in"))
      (node (ref "DA1") (pin "8") (pinfunction "PH_8") (pintype "passive"))
      (node (ref "L1") (pin "2") (pinfunction "2_2") (pintype "passive"))
      (node (ref "VD1") (pin "2") (pinfunction "2_2") (pintype "passive"))
    )
    (net (code "27") (name "Net-(DA1-SS)") (class "Default")
      (node (ref "C11") (pin "2") (pinfunction "2_2") (pintype "power_in"))
      (node (ref "DA1") (pin "4") (pinfunction "SS_4") (pintype "passive"))
    )
    (net (code "28") (name "Net-(DA1-VSENSE)") (class "Default")
      (node (ref "DA1") (pin "5") (pinfunction "VSENSE_5") (pintype "passive"))
      (node (ref "R6") (pin "1") (pinfunction "1_1") (pintype "passive"))
      (node (ref "R7") (pin "2") (pinfunction "2_2") (pintype "passive"))
    )
    (net (code "29") (name "Net-(DD1-OSC_IN)") (class "Default")
      (node (ref "C7") (pin "2") (pinfunction "2_2") (pintype "power_in"))
      (node (ref "DD1") (pin "7") (pinfunction "OSC_IN_7") (pintype "passive"))
      (node (ref "Z1") (pin "1") (pinfunction "1_1") (pintype "passive"))
    )
    (net (code "30") (name "Net-(DD1-OSC_OUT)") (class "Default")
      (node (ref "C8") (pin "2") (pinfunction "2_2") (pintype "power_in"))
      (node (ref "DD1") (pin "8") (pinfunction "OSC_OUT_8") (pintype "passive"))
      (node (ref "Z1") (pin "2") (pinfunction "2_2") (pintype "passive"))
    )
    (net (code "31") (name "Net-(DD1-RXD)") (class "Default")
      (node (ref "DD1") (pin "3") (pinfunction "RXD_3") (pintype "passive"))
      (node (ref "DD3") (pin "42") (pinfunction "PA9_42") (pintype "passive"))
    )
    (net (code "32") (name "Net-(DD1-TXD)") (class "Default")
      (node (ref "DD1") (pin "2") (pinfunction "TXD_2") (pintype "passive"))
      (node (ref "DD3") (pin "43") (pinfunction "PA10_43") (pintype "passive"))
    )
    (net (code "33") (name "Net-(DD2-EN)") (class "Default")
      (node (ref "C9") (pin "1") (pinfunction "1_1") (pintype "power_in"))
      (node (ref "DD2") (pin "3") (pinfunction "EN_3") (pintype "passive"))
      (node (ref "R5") (pin "1") (pinfunction "1_1") (pintype "passive"))
    )
    (net (code "34") (name "Net-(DD3-BOOT)") (class "Default")
      (node (ref "DD3") (pin "60") (pinfunction "BOOT_60") (pintype "passive"))
      (node (ref "SB1") (pin "1") (pinfunction "1_1") (pintype "passive"))
      (node (ref "SB2") (pin "1") (pinfunction "1_1") (pintype "passive"))
    )
    (net (code "35") (name "Net-(DD3-NRST)") (class "Default")
      (node (ref "C24") (pin "2") (pinfunction "2_2") (pintype "power_in"))
      (node (ref "DD3") (pin "7") (pinfunction "NRST_7") (pintype "passive"))
      (node (ref "R8") (pin "2") (pinfunction "2_2") (pintype "passive"))
      (node (ref "SB3") (pin "1") (pinfunction "1_1") (pintype "passive"))
    )
    (net (code "36") (name "Net-(DD3-OSC_IN)") (class "Default")
      (node (ref "C18") (pin "2") (pinfunction "2_2") (pintype "power_in"))
      (node (ref "DD3") (pin "5") (pinfunction "OSC_IN_5") (pintype "passive"))
      (node (ref "Z2") (pin "1") (pinfunction "1_1") (pintype "passive"))
    )
    (net (code "37") (name "Net-(DD3-OSC_OUT)") (class "Default")
      (node (ref "C19") (pin "2") (pinfunction "2_2") (pintype "power_in"))
      (node (ref "DD3") (pin "6") (pinfunction "OSC_OUT_6") (pintype "passive"))
      (node (ref "Z2") (pin "3") (pinfunction "3_3") (pintype "passive"))
    )
    (net (code "38") (name "Net-(R10-Pad2)") (class "Default")
      (node (ref "R10") (pin "2") (pinfunction "2_2") (pintype "passive"))
      (node (ref "R16") (pin "2") (pinfunction "2_2") (pintype "passive"))
      (node (ref "SB6") (pin "1") (pinfunction "1_1") (pintype "passive"))
    )
    (net (code "39") (name "Net-(R11-Pad2)") (class "Default")
      (node (ref "R11") (pin "2") (pinfunction "2_2") (pintype "passive"))
      (node (ref "R17") (pin "2") (pinfunction "2_2") (pintype "passive"))
      (node (ref "SB7") (pin "1") (pinfunction "1_1") (pintype "passive"))
    )
    (net (code "40") (name "Net-(R12-Pad2)") (class "Default")
      (node (ref "R12") (pin "2") (pinfunction "2_2") (pintype "passive"))
      (node (ref "R18") (pin "2") (pinfunction "2_2") (pintype "passive"))
      (node (ref "SB9") (pin "1") (pinfunction "1_1") (pintype "passive"))
    )
    (net (code "41") (name "Net-(R13-Pad2)") (class "Default")
      (node (ref "R13") (pin "2") (pinfunction "2_2") (pintype "passive"))
      (node (ref "R19") (pin "2") (pinfunction "2_2") (pintype "passive"))
      (node (ref "SB8") (pin "1") (pinfunction "1_1") (pintype "passive"))
    )
    (net (code "42") (name "Net-(R14-Pad2)") (class "Default")
      (node (ref "R14") (pin "2") (pinfunction "2_2") (pintype "passive"))
      (node (ref "R20") (pin "2") (pinfunction "2_2") (pintype "passive"))
      (node (ref "SB4") (pin "1") (pinfunction "1_1") (pintype "passive"))
    )
    (net (code "43") (name "Net-(R15-Pad2)") (class "Default")
      (node (ref "R15") (pin "2") (pinfunction "2_2") (pintype "passive"))
      (node (ref "R9") (pin "2") (pinfunction "2_2") (pintype "passive"))
      (node (ref "SB5") (pin "1") (pinfunction "1_1") (pintype "passive"))
    )
    (net (code "44") (name "unconnected-(DD1-CTS-Pad9)") (class "Default")
      (node (ref "DD1") (pin "9") (pinfunction "CTS_9") (pintype "passive"))
    )
    (net (code "45") (name "unconnected-(DD1-DCD-Pad12)") (class "Default")
      (node (ref "DD1") (pin "12") (pinfunction "DCD_12") (pintype "passive"))
    )
    (net (code "46") (name "unconnected-(DD1-DSR-Pad10)") (class "Default")
      (node (ref "DD1") (pin "10") (pinfunction "DSR_10") (pintype "passive"))
    )
    (net (code "47") (name "unconnected-(DD1-DTR-Pad13)") (class "Default")
      (node (ref "DD1") (pin "13") (pinfunction "DTR_13") (pintype "passive"))
    )
    (net (code "48") (name "unconnected-(DD1-R232-Pad15)") (class "Default")
      (node (ref "DD1") (pin "15") (pinfunction "R232_15") (pintype "passive"))
    )
    (net (code "49") (name "unconnected-(DD1-RI-Pad11)") (class "Default")
      (node (ref "DD1") (pin "11") (pinfunction "RI_11") (pintype "passive"))
    )
    (net (code "50") (name "unconnected-(DD1-RTS-Pad14)") (class "Default")
      (node (ref "DD1") (pin "14") (pinfunction "RTS_14") (pintype "passive"))
    )
    (net (code "51") (name "unconnected-(DD2-CLK-Pad20)") (class "Default")
      (node (ref "DD2") (pin "20") (pinfunction "CLK_20") (pintype "passive"))
    )
    (net (code "52") (name "unconnected-(DD2-CMD-Pad19)") (class "Default")
      (node (ref "DD2") (pin "19") (pinfunction "CMD_19") (pintype "passive"))
    )
    (net (code "53") (name "unconnected-(DD2-IO0-Pad25)") (class "Default")
      (node (ref "DD2") (pin "25") (pinfunction "IO0_25") (pintype "passive"))
    )
    (net (code "54") (name "unconnected-(DD2-IO1-Pad24)") (class "Default")
      (node (ref "DD2") (pin "24") (pinfunction "IO1_24") (pintype "passive"))
    )
    (net (code "55") (name "unconnected-(DD2-IO4-Pad26)") (class "Default")
      (node (ref "DD2") (pin "26") (pinfunction "IO4_26") (pintype "passive"))
    )
    (net (code "56") (name "unconnected-(DD2-IO5-Pad29)") (class "Default")
      (node (ref "DD2") (pin "29") (pinfunction "IO5_29") (pintype "passive"))
    )
    (net (code "57") (name "unconnected-(DD2-IO12-Pad14)") (class "Default")
      (node (ref "DD2") (pin "14") (pinfunction "IO12_14") (pintype "passive"))
    )
    (net (code "58") (name "unconnected-(DD2-IO13-Pad16)") (class "Default")
      (node (ref "DD2") (pin "16") (pinfunction "IO13_16") (pintype "passive"))
    )
    (net (code "59") (name "unconnected-(DD2-IO14-Pad13)") (class "Default")
      (node (ref "DD2") (pin "13") (pinfunction "IO14_13") (pintype "passive"))
    )
    (net (code "60") (name "unconnected-(DD2-IO15-Pad23)") (class "Default")
      (node (ref "DD2") (pin "23") (pinfunction "IO15_23") (pintype "passive"))
    )
    (net (code "61") (name "unconnected-(DD2-IO16-Pad27)") (class "Default")
      (node (ref "DD2") (pin "27") (pinfunction "IO16_27") (pintype "passive"))
    )
    (net (code "62") (name "unconnected-(DD2-IO17-Pad28)") (class "Default")
      (node (ref "DD2") (pin "28") (pinfunction "IO17_28") (pintype "passive"))
    )
    (net (code "63") (name "unconnected-(DD2-IO18-Pad30)") (class "Default")
      (node (ref "DD2") (pin "30") (pinfunction "IO18_30") (pintype "passive"))
    )
    (net (code "64") (name "unconnected-(DD2-IO19-Pad31)") (class "Default")
      (node (ref "DD2") (pin "31") (pinfunction "IO19_31") (pintype "passive"))
    )
    (net (code "65") (name "unconnected-(DD2-IO21-Pad33)") (class "Default")
      (node (ref "DD2") (pin "33") (pinfunction "IO21_33") (pintype "passive"))
    )
    (net (code "66") (name "unconnected-(DD2-IO22-Pad36)") (class "Default")
      (node (ref "DD2") (pin "36") (pinfunction "IO22_36") (pintype "passive"))
    )
    (net (code "67") (name "unconnected-(DD2-IO23-Pad37)") (class "Default")
      (node (ref "DD2") (pin "37") (pinfunction "IO23_37") (pintype "passive"))
    )
    (net (code "68") (name "unconnected-(DD2-IO25-Pad10)") (class "Default")
      (node (ref "DD2") (pin "10") (pinfunction "IO25_10") (pintype "passive"))
    )
    (net (code "69") (name "unconnected-(DD2-IO26-Pad11)") (class "Default")
      (node (ref "DD2") (pin "11") (pinfunction "IO26_11") (pintype "passive"))
    )
    (net (code "70") (name "unconnected-(DD2-IO27-Pad12)") (class "Default")
      (node (ref "DD2") (pin "12") (pinfunction "IO27_12") (pintype "passive"))
    )
    (net (code "71") (name "unconnected-(DD2-IO32-Pad8)") (class "Default")
      (node (ref "DD2") (pin "8") (pinfunction "IO32_8") (pintype "passive"))
    )
    (net (code "72") (name "unconnected-(DD2-IO33-Pad9)") (class "Default")
      (node (ref "DD2") (pin "9") (pinfunction "IO33_9") (pintype "passive"))
    )
    (net (code "73") (name "unconnected-(DD2-IO34-Pad6)") (class "Default")
      (node (ref "DD2") (pin "6") (pinfunction "IO34_6") (pintype "passive"))
    )
    (net (code "74") (name "unconnected-(DD2-IO35-Pad7)") (class "Default")
      (node (ref "DD2") (pin "7") (pinfunction "IO35_7") (pintype "passive"))
    )
    (net (code "75") (name "unconnected-(DD2-NC-Pad32)") (class "Default")
      (node (ref "DD2") (pin "32") (pinfunction "NC_32") (pintype "passive"))
    )
    (net (code "76") (name "unconnected-(DD2-SD0-Pad21)") (class "Default")
      (node (ref "DD2") (pin "21") (pinfunction "SD0_21") (pintype "passive"))
    )
    (net (code "77") (name "unconnected-(DD2-SD1-Pad22)") (class "Default")
      (node (ref "DD2") (pin "22") (pinfunction "SD1_22") (pintype "passive"))
    )
    (net (code "78") (name "unconnected-(DD2-SD2-Pad17)") (class "Default")
      (node (ref "DD2") (pin "17") (pinfunction "SD2_17") (pintype "passive"))
    )
    (net (code "79") (name "unconnected-(DD2-SD3-Pad18)") (class "Default")
      (node (ref "DD2") (pin "18") (pinfunction "SD3_18") (pintype "passive"))
    )
    (net (code "80") (name "unconnected-(DD2-SENSOR_VN-Pad5)") (class "Default")
      (node (ref "DD2") (pin "5") (pinfunction "SENSOR_VN_5") (pintype "passive"))
    )
    (net (code "81") (name "unconnected-(DD2-SENSOR_VP-Pad4)") (class "Default")
      (node (ref "DD2") (pin "4") (pinfunction "SENSOR_VP_4") (pintype "passive"))
    )
    (net (code "82") (name "unconnected-(DD3-PA0-Pad14)") (class "Default")
      (node (ref "DD3") (pin "14") (pinfunction "PA0_14") (pintype "passive"))
    )
    (net (code "83") (name "unconnected-(DD3-PA1-Pad15)") (class "Default")
      (node (ref "DD3") (pin "15") (pinfunction "PA1_15") (pintype "passive"))
    )
    (net (code "84") (name "unconnected-(DD3-PA4-Pad20)") (class "Default")
      (node (ref "DD3") (pin "20") (pinfunction "PA4_20") (pintype "passive"))
    )
    (net (code "85") (name "unconnected-(DD3-PA5-Pad21)") (class "Default")
      (node (ref "DD3") (pin "21") (pinfunction "PA5_21") (pintype "passive"))
    )
    (net (code "86") (name "unconnected-(DD3-PA6-Pad22)") (class "Default")
      (node (ref "DD3") (pin "22") (pinfunction "PA6_22") (pintype "passive"))
    )
    (net (code "87") (name "unconnected-(DD3-PA7-Pad23)") (class "Default")
      (node (ref "DD3") (pin "23") (pinfunction "PA7_23") (pintype "passive"))
    )
    (net (code "88") (name "unconnected-(DD3-PA8-Pad41)") (class "Default")
      (node (ref "DD3") (pin "41") (pinfunction "PA8_41") (pintype "passive"))
    )
    (net (code "89") (name "unconnected-(DD3-PA11-Pad44)") (class "Default")
      (node (ref "DD3") (pin "44") (pinfunction "PA11_44") (pintype "passive"))
    )
    (net (code "90") (name "unconnected-(DD3-PA12-Pad45)") (class "Default")
      (node (ref "DD3") (pin "45") (pinfunction "PA12_45") (pintype "passive"))
    )
    (net (code "91") (name "unconnected-(DD3-PA13-Pad46)") (class "Default")
      (node (ref "DD3") (pin "46") (pinfunction "PA13_46") (pintype "passive"))
    )
    (net (code "92") (name "unconnected-(DD3-PA14-Pad49)") (class "Default")
      (node (ref "DD3") (pin "49") (pinfunction "PA14_49") (pintype "passive"))
    )
    (net (code "93") (name "unconnected-(DD3-PA15-Pad50)") (class "Default")
      (node (ref "DD3") (pin "50") (pinfunction "PA15_50") (pintype "passive"))
    )
    (net (code "94") (name "unconnected-(DD3-PB0-Pad26)") (class "Default")
      (node (ref "DD3") (pin "26") (pinfunction "PB0_26") (pintype "passive"))
    )
    (net (code "95") (name "unconnected-(DD3-PB1-Pad27)") (class "Default")
      (node (ref "DD3") (pin "27") (pinfunction "PB1_27") (pintype "passive"))
    )
    (net (code "96") (name "unconnected-(DD3-PB2-Pad28)") (class "Default")
      (node (ref "DD3") (pin "28") (pinfunction "PB2_28") (pintype "passive"))
    )
    (net (code "97") (name "unconnected-(DD3-PB3-Pad55)") (class "Default")
      (node (ref "DD3") (pin "55") (pinfunction "PB3_55") (pintype "passive"))
    )
    (net (code "98") (name "unconnected-(DD3-PB4-Pad56)") (class "Default")
      (node (ref "DD3") (pin "56") (pinfunction "PB4_56") (pintype "passive"))
    )
    (net (code "99") (name "unconnected-(DD3-PB5-Pad57)") (class "Default")
      (node (ref "DD3") (pin "57") (pinfunction "PB5_57") (pintype "passive"))
    )
    (net (code "100") (name "unconnected-(DD3-PB6-Pad58)") (class "Default")
      (node (ref "DD3") (pin "58") (pinfunction "PB6_58") (pintype "passive"))
    )
    (net (code "101") (name "unconnected-(DD3-PB7-Pad59)") (class "Default")
      (node (ref "DD3") (pin "59") (pinfunction "PB7_59") (pintype "passive"))
    )
    (net (code "102") (name "unconnected-(DD3-PB8-Pad61)") (class "Default")
      (node (ref "DD3") (pin "61") (pinfunction "PB8_61") (pintype "passive"))
    )
    (net (code "103") (name "unconnected-(DD3-PB9-Pad62)") (class "Default")
      (node (ref "DD3") (pin "62") (pinfunction "PB9_62") (pintype "passive"))
    )
    (net (code "104") (name "unconnected-(DD3-PB10-Pad29)") (class "Default")
      (node (ref "DD3") (pin "29") (pinfunction "PB10_29") (pintype "passive"))
    )
    (net (code "105") (name "unconnected-(DD3-PB11-Pad30)") (class "Default")
      (node (ref "DD3") (pin "30") (pinfunction "PB11_30") (pintype "passive"))
    )
    (net (code "106") (name "unconnected-(DD3-PC0-Pad8)") (class "Default")
      (node (ref "DD3") (pin "8") (pinfunction "PC0_8") (pintype "passive"))
    )
    (net (code "107") (name "unconnected-(DD3-PC1-Pad9)") (class "Default")
      (node (ref "DD3") (pin "9") (pinfunction "PC1_9") (pintype "passive"))
    )
    (net (code "108") (name "unconnected-(DD3-PC2-Pad10)") (class "Default")
      (node (ref "DD3") (pin "10") (pinfunction "PC2_10") (pintype "passive"))
    )
    (net (code "109") (name "unconnected-(DD3-PC3-Pad11)") (class "Default")
      (node (ref "DD3") (pin "11") (pinfunction "PC3_11") (pintype "passive"))
    )
    (net (code "110") (name "unconnected-(DD3-PC4-Pad24)") (class "Default")
      (node (ref "DD3") (pin "24") (pinfunction "PC4_24") (pintype "passive"))
    )
    (net (code "111") (name "unconnected-(DD3-PC5-Pad25)") (class "Default")
      (node (ref "DD3") (pin "25") (pinfunction "PC5_25") (pintype "passive"))
    )
    (net (code "112") (name "unconnected-(DD3-PC8-Pad39)") (class "Default")
      (node (ref "DD3") (pin "39") (pinfunction "PC8_39") (pintype "passive"))
    )
    (net (code "113") (name "unconnected-(DD3-PC9-Pad40)") (class "Default")
      (node (ref "DD3") (pin "40") (pinfunction "PC9_40") (pintype "passive"))
    )
    (net (code "114") (name "unconnected-(DD3-PC10-Pad51)") (class "Default")
      (node (ref "DD3") (pin "51") (pinfunction "PC10_51") (pintype "passive"))
    )
    (net (code "115") (name "unconnected-(DD3-PC11-Pad52)") (class "Default")
      (node (ref "DD3") (pin "52") (pinfunction "PC11_52") (pintype "passive"))
    )
    (net (code "116") (name "unconnected-(DD3-PC12-Pad53)") (class "Default")
      (node (ref "DD3") (pin "53") (pinfunction "PC12_53") (pintype "passive"))
    )
    (net (code "117") (name "unconnected-(DD3-PC13-Pad2)") (class "Default")
      (node (ref "DD3") (pin "2") (pinfunction "PC13_2") (pintype "passive"))
    )
    (net (code "118") (name "unconnected-(DD3-PC14-Pad3)") (class "Default")
      (node (ref "DD3") (pin "3") (pinfunction "PC14_3") (pintype "passive"))
    )
    (net (code "119") (name "unconnected-(DD3-PC15-Pad4)") (class "Default")
      (node (ref "DD3") (pin "4") (pinfunction "PC15_4") (pintype "passive"))
    )
    (net (code "120") (name "unconnected-(DD3-PD2-Pad54)") (class "Default")
      (node (ref "DD3") (pin "54") (pinfunction "PD2_54") (pintype "passive"))
    )
    (net (code "121") (name "unconnected-(DD3-VBAT-Pad1)") (class "Default")
      (node (ref "DD3") (pin "1") (pinfunction "VBAT_1") (pintype "power_in"))
    )
  )
)
